# External_Connectors.net
KiCad netlist of a schematic drawn in Altium Designer
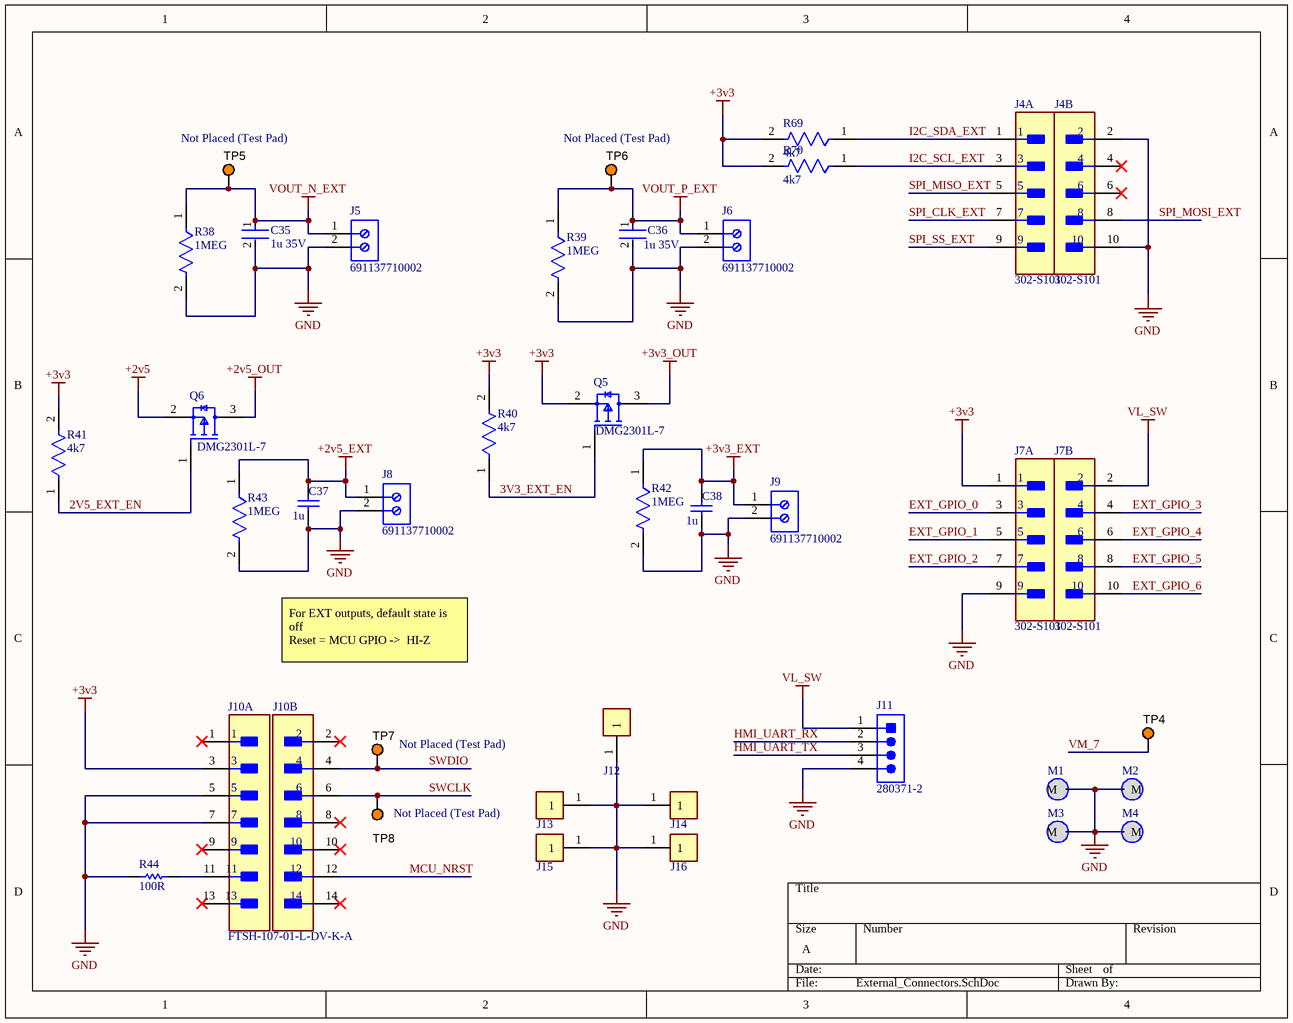
[diagram p0: External_Connectors.SchDoc]

(export (version "E")
  (design (tool "Eeschema 10.0.6"))
  (components
    (comp (ref "C35")
      (value "1u 35V")
      (footprint "FP-CL10-IPC_C")
      (description "Cap Ceramic 1uF 35V X5R ±10% Pad SMD 0603 +85°C T/R")
      (fields (field (name "TOLERANCE") "10%"))
      (libsource (lib "Altium Content Vault") (part "b4654b650e69147ec39a6b967a45e02"))
    )
    (comp (ref "C36")
      (value "1u 35V")
      (footprint "FP-CL10-IPC_C")
      (description "Cap Ceramic 1uF 35V X5R ±10% Pad SMD 0603 +85°C T/R")
      (fields (field (name "TOLERANCE") "10%"))
      (libsource (lib "Altium Content Vault") (part "b4654b650e69147ec39a6b967a45e02"))
    )
    (comp (ref "C37")
      (value "1u")
      (footprint "CAPC2013X145X50NL20T25")
      (fields (field (name "PART NUMBER") "C0805C106M9RACTU") (field (name "MANUFACTURER") "Kemet"))
      (libsource (lib "Altium Content Vault") (part "CAP"))
    )
    (comp (ref "C38")
      (value "1u")
      (footprint "CAPC2013X145X50NL20T25")
      (fields (field (name "PART NUMBER") "C0805C106M9RACTU") (field (name "MANUFACTURER") "Kemet"))
      (libsource (lib "Altium Content Vault") (part "CAP"))
    )
    (comp (ref "J4")
      (value "302-S101")
      (footprint "FP-302-S101-MFG")
      (description "CONN HEADER VERT 10POS 2.54MM")
      (libsource (lib "Altium Content Vault") (part "544f42128f4185dcb88ce1ce9bf1982"))
    )
    (comp (ref "J5")
      (value "691137710002")
      (footprint "691137710002")
      (libsource (lib "Altium Content Vault") (part "TBL - 1R - 02P - Screw"))
    )
    (comp (ref "J6")
      (value "691137710002")
      (footprint "691137710002")
      (libsource (lib "Altium Content Vault") (part "TBL - 1R - 02P - Screw"))
    )
    (comp (ref "J7")
      (value "302-S101")
      (footprint "FP-302-S101-MFG")
      (description "CONN HEADER VERT 10POS 2.54MM")
      (libsource (lib "Altium Content Vault") (part "544f42128f4185dcb88ce1ce9bf1982"))
    )
    (comp (ref "J8")
      (value "691137710002")
      (footprint "691137710002")
      (libsource (lib "Altium Content Vault") (part "TBL - 1R - 02P - Screw"))
    )
    (comp (ref "J9")
      (value "691137710002")
      (footprint "691137710002")
      (libsource (lib "Altium Content Vault") (part "TBL - 1R - 02P - Screw"))
    )
    (comp (ref "J10")
      (value "FTSH-107-01-L-DV-K-A")
      (footprint "FP-FTSH-107-01-L-DV-K-A-MFG")
      (description "CONN HEADER SMD 14POS 1.27MM")
      (libsource (lib "Altium Content Vault") (part "45cc164b9edde9e1ad516d884ad4e1e"))
    )
    (comp (ref "J11")
      (value "280371-2")
      (footprint "TECO-280371-2_V")
      (fields (field (name "MANUFACTURER") "TE Connectivity"))
      (libsource (lib "Altium Content Vault") (part "CN-1P-M-R4"))
    )
    (comp (ref "J12")
      (value "5001")
      (footprint "FP-5001-MFG")
      (description "PC TEST POINT MINIATURE BLACK")
      (libsource (lib "Altium Content Vault") (part "1e4615820a309e3ce90f9e6d957b7fa"))
    )
    (comp (ref "J13")
      (value "5001")
      (footprint "FP-5001-MFG")
      (description "PC TEST POINT MINIATURE BLACK")
      (libsource (lib "") (part "1e4615820a309e3ce90f9e6d957b7fa_1"))
    )
    (comp (ref "J14")
      (value "5001")
      (footprint "FP-5001-MFG")
      (description "PC TEST POINT MINIATURE BLACK")
      (libsource (lib "Altium Content Vault") (part "1e4615820a309e3ce90f9e6d957b7fa"))
    )
    (comp (ref "J15")
      (value "5001")
      (footprint "FP-5001-MFG")
      (description "PC TEST POINT MINIATURE BLACK")
      (libsource (lib "") (part "1e4615820a309e3ce90f9e6d957b7fa_1"))
    )
    (comp (ref "J16")
      (value "5001")
      (footprint "FP-5001-MFG")
      (description "PC TEST POINT MINIATURE BLACK")
      (libsource (lib "Altium Content Vault") (part "1e4615820a309e3ce90f9e6d957b7fa"))
    )
    (comp (ref "M1")
      (value "Mounting_Holes")
      (footprint "Mountiing_Hole")
      (libsource (lib "USBC_Power_Supply") (part "Mounting_Holes"))
    )
    (comp (ref "M2")
      (value "Mounting_Holes")
      (footprint "Mountiing_Hole")
      (libsource (lib "USBC_Power_Supply") (part "Mounting_Holes"))
    )
    (comp (ref "M3")
      (value "Mounting_Holes")
      (footprint "Mountiing_Hole")
      (libsource (lib "USBC_Power_Supply") (part "Mounting_Holes"))
    )
    (comp (ref "M4")
      (value "Mounting_Holes")
      (footprint "Mountiing_Hole")
      (libsource (lib "USBC_Power_Supply") (part "Mounting_Holes"))
    )
    (comp (ref "Q5")
      (value "DMG2301L-7")
      (footprint "FP-SOT23-MFG")
      (description "MOSFET P-CH 20V 3A SOT23")
      (fields
        (field (name "MANUFACTURER") "Diodes Inc.")
        (field (name "OCTOPART") "https://octopart.com/dmg2301l-7-diodes+inc.-67250456")
      )
      (libsource (lib "Altium Content Vault") (part "b8f99f9e586195791e7fb11725ebaeb"))
    )
    (comp (ref "Q6")
      (value "DMG2301L-7")
      (footprint "FP-SOT23-MFG")
      (description "MOSFET P-CH 20V 3A SOT23")
      (fields
        (field (name "MANUFACTURER") "Diodes Inc.")
        (field (name "OCTOPART") "https://octopart.com/dmg2301l-7-diodes+inc.-67250456")
      )
      (libsource (lib "Altium Content Vault") (part "b8f99f9e586195791e7fb11725ebaeb"))
    )
    (comp (ref "R38")
      (value "1MEG")
      (footprint "FP-AC0603-IPC_A")
      (description "RES 1MΩ 1.00% 0.1W 0603")
      (fields (field (name "TOLERANCE") "1%"))
      (libsource (lib "Altium Content Vault") (part "1029c3af85768c4190bb7ad29bc67b5"))
    )
    (comp (ref "R39")
      (value "1MEG")
      (footprint "FP-AC0603-IPC_A")
      (description "RES 1MΩ 1.00% 0.1W 0603")
      (fields (field (name "TOLERANCE") "1%"))
      (libsource (lib "Altium Content Vault") (part "1029c3af85768c4190bb7ad29bc67b5"))
    )
    (comp (ref "R40")
      (value "4k7")
      (footprint "FP-AC0603-IPC_A")
      (description "RES 4.7KΩ 1.00% 0.1W 0603")
      (fields (field (name "TOLERANCE") "1%"))
      (libsource (lib "Altium Content Vault") (part "1029c3af85768c4190bb7ad29bc67b5"))
    )
    (comp (ref "R41")
      (value "4k7")
      (footprint "FP-AC0603-IPC_A")
      (description "RES 4.7KΩ 1.00% 0.1W 0603")
      (fields (field (name "TOLERANCE") "1%"))
      (libsource (lib "Altium Content Vault") (part "1029c3af85768c4190bb7ad29bc67b5"))
    )
    (comp (ref "R42")
      (value "1MEG")
      (footprint "FP-AC0603-IPC_A")
      (description "RES 1MΩ 1.00% 0.1W 0603")
      (fields (field (name "TOLERANCE") "1%"))
      (libsource (lib "Altium Content Vault") (part "1029c3af85768c4190bb7ad29bc67b5"))
    )
    (comp (ref "R43")
      (value "1MEG")
      (footprint "FP-AC0603-IPC_A")
      (description "RES 1MΩ 1.00% 0.1W 0603")
      (fields (field (name "TOLERANCE") "1%"))
      (libsource (lib "Altium Content Vault") (part "1029c3af85768c4190bb7ad29bc67b5"))
    )
    (comp (ref "R44")
      (value "100R")
      (footprint "RESC1608X55X30NL15T15")
      (fields (field (name "PART NUMBER") "ERJ-3EKF1502V") (field (name "MANUFACTURER") "Panasonic"))
      (libsource (lib "Altium Content Vault") (part "RES"))
    )
    (comp (ref "R69")
      (value "4k7")
      (footprint "FP-AC0603-IPC_A")
      (description "RES 4.7KΩ 1.00% 0.1W 0603")
      (fields (field (name "TOLERANCE") "1%"))
      (libsource (lib "Altium Content Vault") (part "1029c3af85768c4190bb7ad29bc67b5"))
    )
    (comp (ref "R70")
      (value "4k7")
      (footprint "FP-AC0603-IPC_A")
      (description "RES 4.7KΩ 1.00% 0.1W 0603")
      (fields (field (name "TOLERANCE") "1%"))
      (libsource (lib "Altium Content Vault") (part "1029c3af85768c4190bb7ad29bc67b5"))
    )
    (comp (ref "TP4")
      (value "5003")
      (footprint "KSTN-5003")
      (description "Test Point, Orange, 1-Pin THD, RoHS")
      (libsource (lib "Altium Content Vault") (part "TESTPOINT_ORANGE"))
    )
    (comp (ref "TP5")
      (value "5003")
      (footprint "KSTN-5003")
      (description "Test Point, Orange, 1-Pin THD, RoHS")
      (libsource (lib "Altium Content Vault") (part "TESTPOINT_ORANGE"))
    )
    (comp (ref "TP6")
      (value "5003")
      (footprint "KSTN-5003")
      (description "Test Point, Orange, 1-Pin THD, RoHS")
      (libsource (lib "Altium Content Vault") (part "TESTPOINT_ORANGE"))
    )
    (comp (ref "TP7")
      (value "5003")
      (footprint "KSTN-5003")
      (description "Test Point, Orange, 1-Pin THD, RoHS")
      (libsource (lib "Altium Content Vault") (part "TESTPOINT_ORANGE"))
    )
    (comp (ref "TP8")
      (value "5003")
      (footprint "KSTN-5003")
      (description "Test Point, Orange, 1-Pin THD, RoHS")
      (libsource (lib "Altium Content Vault") (part "TESTPOINT_ORANGE"))
    )
  )
  (nets
    (net (code "1") (name "+2v5") (class "Default")
      (node (ref "Q6") (pin "2") (pinfunction "S_2") (pintype "passive"))
    )
    (net (code "2") (name "+2v5_EXT") (class "Default")
      (node (ref "C37") (pin "2") (pinfunction "2_2") (pintype "passive"))
      (node (ref "J8") (pin "1") (pinfunction "1_1") (pintype "passive"))
      (node (ref "R43") (pin "1") (pinfunction "1_1") (pintype "passive"))
    )
    (net (code "3") (name "+2v5_OUT") (class "Default")
      (node (ref "Q6") (pin "3") (pinfunction "D_3") (pintype "passive"))
    )
    (net (code "4") (name "+3v3") (class "Default")
      (node (ref "J10") (pin "3") (pinfunction "3_3") (pintype "passive"))
      (node (ref "J7") (pin "1") (pinfunction "1_1") (pintype "passive"))
      (node (ref "Q5") (pin "2") (pinfunction "S_2") (pintype "passive"))
      (node (ref "R40") (pin "2") (pinfunction "2_2") (pintype "passive"))
      (node (ref "R41") (pin "2") (pinfunction "2_2") (pintype "passive"))
      (node (ref "R69") (pin "2") (pinfunction "2_2") (pintype "passive"))
      (node (ref "R70") (pin "2") (pinfunction "2_2") (pintype "passive"))
    )
    (net (code "5") (name "+3v3_EXT") (class "Default")
      (node (ref "C38") (pin "2") (pinfunction "2_2") (pintype "passive"))
      (node (ref "J9") (pin "1") (pinfunction "1_1") (pintype "passive"))
      (node (ref "R42") (pin "1") (pinfunction "1_1") (pintype "passive"))
    )
    (net (code "6") (name "+3v3_OUT") (class "Default")
      (node (ref "Q5") (pin "3") (pinfunction "D_3") (pintype "passive"))
    )
    (net (code "7") (name "/2V5_EXT_EN") (class "Default")
      (node (ref "Q6") (pin "1") (pinfunction "G_1") (pintype "passive"))
      (node (ref "R41") (pin "1") (pinfunction "1_1") (pintype "passive"))
    )
    (net (code "8") (name "/3V3_EXT_EN") (class "Default")
      (node (ref "Q5") (pin "1") (pinfunction "G_1") (pintype "passive"))
      (node (ref "R40") (pin "1") (pinfunction "1_1") (pintype "passive"))
    )
    (net (code "9") (name "/EXT_GPIO_0") (class "Default")
      (node (ref "J7") (pin "3") (pinfunction "3_3") (pintype "passive"))
    )
    (net (code "10") (name "/EXT_GPIO_1") (class "Default")
      (node (ref "J7") (pin "5") (pinfunction "5_5") (pintype "passive"))
    )
    (net (code "11") (name "/EXT_GPIO_2") (class "Default")
      (node (ref "J7") (pin "7") (pinfunction "7_7") (pintype "passive"))
    )
    (net (code "12") (name "/EXT_GPIO_3") (class "Default")
      (node (ref "J7") (pin "4") (pinfunction "4_4") (pintype "passive"))
    )
    (net (code "13") (name "/EXT_GPIO_4") (class "Default")
      (node (ref "J7") (pin "6") (pinfunction "6_6") (pintype "passive"))
    )
    (net (code "14") (name "/EXT_GPIO_5") (class "Default")
      (node (ref "J7") (pin "8") (pinfunction "8_8") (pintype "passive"))
    )
    (net (code "15") (name "/EXT_GPIO_6") (class "Default")
      (node (ref "J7") (pin "10") (pinfunction "10_10") (pintype "passive"))
    )
    (net (code "16") (name "/HMI_UART_RX") (class "Default")
      (node (ref "J11") (pin "2") (pinfunction "2_2") (pintype "passive"))
    )
    (net (code "17") (name "/HMI_UART_TX") (class "Default")
      (node (ref "J11") (pin "3") (pinfunction "3_3") (pintype "passive"))
    )
    (net (code "18") (name "/I2C_SCL_EXT") (class "Default")
      (node (ref "J4") (pin "3") (pinfunction "3_3") (pintype "passive"))
      (node (ref "R70") (pin "1") (pinfunction "1_1") (pintype "passive"))
    )
    (net (code "19") (name "/I2C_SDA_EXT") (class "Default")
      (node (ref "J4") (pin "1") (pinfunction "1_1") (pintype "passive"))
      (node (ref "R69") (pin "1") (pinfunction "1_1") (pintype "passive"))
    )
    (net (code "20") (name "/MCU_NRST") (class "Default")
      (node (ref "J10") (pin "12") (pinfunction "12_12") (pintype "passive"))
    )
    (net (code "21") (name "/SPI_CLK_EXT") (class "Default")
      (node (ref "J4") (pin "7") (pinfunction "7_7") (pintype "passive"))
    )
    (net (code "22") (name "/SPI_MISO_EXT") (class "Default")
      (node (ref "J4") (pin "5") (pinfunction "5_5") (pintype "passive"))
    )
    (net (code "23") (name "/SPI_MOSI_EXT") (class "Default")
      (node (ref "J4") (pin "8") (pinfunction "8_8") (pintype "passive"))
    )
    (net (code "24") (name "/SPI_SS_EXT") (class "Default")
      (node (ref "J4") (pin "9") (pinfunction "9_9") (pintype "passive"))
    )
    (net (code "25") (name "/SWCLK") (class "Default")
      (node (ref "J10") (pin "6") (pinfunction "6_6") (pintype "passive"))
      (node (ref "TP8") (pin "1") (pinfunction "1_1") (pintype "passive"))
    )
    (net (code "26") (name "/SWDIO") (class "Default")
      (node (ref "J10") (pin "4") (pinfunction "4_4") (pintype "passive"))
      (node (ref "TP7") (pin "1") (pinfunction "1_1") (pintype "passive"))
    )
    (net (code "27") (name "/VM_7") (class "Default")
      (node (ref "TP4") (pin "1") (pinfunction "1_1") (pintype "passive"))
    )
    (net (code "28") (name "GND") (class "Default")
      (node (ref "C35") (pin "2") (pinfunction "2_2") (pintype "passive"))
      (node (ref "C36") (pin "2") (pinfunction "2_2") (pintype "passive"))
      (node (ref "C37") (pin "1") (pinfunction "1_1") (pintype "passive"))
      (node (ref "C38") (pin "1") (pinfunction "1_1") (pintype "passive"))
      (node (ref "J10") (pin "5") (pinfunction "5_5") (pintype "passive"))
      (node (ref "J10") (pin "7") (pinfunction "7_7") (pintype "passive"))
      (node (ref "J11") (pin "4") (pinfunction "4_4") (pintype "passive"))
      (node (ref "J12") (pin "1") (pinfunction "1_1") (pintype "passive"))
      (node (ref "J13") (pin "1") (pinfunction "1_1") (pintype "passive"))
      (node (ref "J14") (pin "1") (pinfunction "1_1") (pintype "passive"))
      (node (ref "J15") (pin "1") (pinfunction "1_1") (pintype "passive"))
      (node (ref "J16") (pin "1") (pinfunction "1_1") (pintype "passive"))
      (node (ref "J4") (pin "10") (pinfunction "10_10") (pintype "passive"))
      (node (ref "J4") (pin "2") (pinfunction "2_2") (pintype "passive"))
      (node (ref "J5") (pin "2") (pinfunction "2_2") (pintype "passive"))
      (node (ref "J6") (pin "2") (pinfunction "2_2") (pintype "passive"))
      (node (ref "J7") (pin "9") (pinfunction "9_9") (pintype "passive"))
      (node (ref "J8") (pin "2") (pinfunction "2_2") (pintype "passive"))
      (node (ref "J9") (pin "2") (pinfunction "2_2") (pintype "passive"))
      (node (ref "M1") (pin "M") (pinfunction "M_M") (pintype "passive"))
      (node (ref "M2") (pin "M") (pinfunction "M_M") (pintype "passive"))
      (node (ref "M3") (pin "M") (pinfunction "M_M") (pintype "passive"))
      (node (ref "M4") (pin "M") (pinfunction "M_M") (pintype "passive"))
      (node (ref "R38") (pin "2") (pinfunction "2_2") (pintype "passive"))
      (node (ref "R39") (pin "2") (pinfunction "2_2") (pintype "passive"))
      (node (ref "R42") (pin "2") (pinfunction "2_2") (pintype "passive"))
      (node (ref "R43") (pin "2") (pinfunction "2_2") (pintype "passive"))
      (node (ref "R44") (pin "2") (pinfunction "2_2") (pintype "passive"))
    )
    (net (code "29") (name "Net-(J10-Pad11)") (class "Default")
      (node (ref "J10") (pin "11") (pinfunction "11_11") (pintype "passive"))
      (node (ref "R44") (pin "1") (pinfunction "1_1") (pintype "passive"))
    )
    (net (code "30") (name "VL_SW") (class "Default")
      (node (ref "J11") (pin "1") (pinfunction "1_1") (pintype "passive"))
      (node (ref "J7") (pin "2") (pinfunction "2_2") (pintype "passive"))
    )
    (net (code "31") (name "VOUT_N_EXT") (class "Default")
      (node (ref "C35") (pin "1") (pinfunction "1_1") (pintype "passive"))
      (node (ref "J5") (pin "1") (pinfunction "1_1") (pintype "passive"))
      (node (ref "R38") (pin "1") (pinfunction "1_1") (pintype "passive"))
      (node (ref "TP5") (pin "1") (pinfunction "1_1") (pintype "passive"))
    )
    (net (code "32") (name "VOUT_P_EXT") (class "Default")
      (node (ref "C36") (pin "1") (pinfunction "1_1") (pintype "passive"))
      (node (ref "J6") (pin "1") (pinfunction "1_1") (pintype "passive"))
      (node (ref "R39") (pin "1") (pinfunction "1_1") (pintype "passive"))
      (node (ref "TP6") (pin "1") (pinfunction "1_1") (pintype "passive"))
    )
    (net (code "33") (name "unconnected-(J4-Pad4)") (class "Default")
      (node (ref "J4") (pin "4") (pinfunction "4_4") (pintype "passive+no_connect"))
    )
    (net (code "34") (name "unconnected-(J4-Pad6)") (class "Default")
      (node (ref "J4") (pin "6") (pinfunction "6_6") (pintype "passive+no_connect"))
    )
    (net (code "35") (name "unconnected-(J10-Pad1)") (class "Default")
      (node (ref "J10") (pin "1") (pinfunction "1_1") (pintype "passive+no_connect"))
    )
    (net (code "36") (name "unconnected-(J10-Pad2)") (class "Default")
      (node (ref "J10") (pin "2") (pinfunction "2_2") (pintype "passive+no_connect"))
    )
    (net (code "37") (name "unconnected-(J10-Pad8)") (class "Default")
      (node (ref "J10") (pin "8") (pinfunction "8_8") (pintype "passive+no_connect"))
    )
    (net (code "38") (name "unconnected-(J10-Pad9)") (class "Default")
      (node (ref "J10") (pin "9") (pinfunction "9_9") (pintype "passive+no_connect"))
    )
    (net (code "39") (name "unconnected-(J10-Pad10)") (class "Default")
      (node (ref "J10") (pin "10") (pinfunction "10_10") (pintype "passive+no_connect"))
    )
    (net (code "40") (name "unconnected-(J10-Pad13)") (class "Default")
      (node (ref "J10") (pin "13") (pinfunction "13_13") (pintype "passive+no_connect"))
    )
    (net (code "41") (name "unconnected-(J10-Pad14)") (class "Default")
      (node (ref "J10") (pin "14") (pinfunction "14_14") (pintype "passive+no_connect"))
    )
  )
)
